# frontscript.net
KiCad netlist of a schematic drawn in Altium Designer
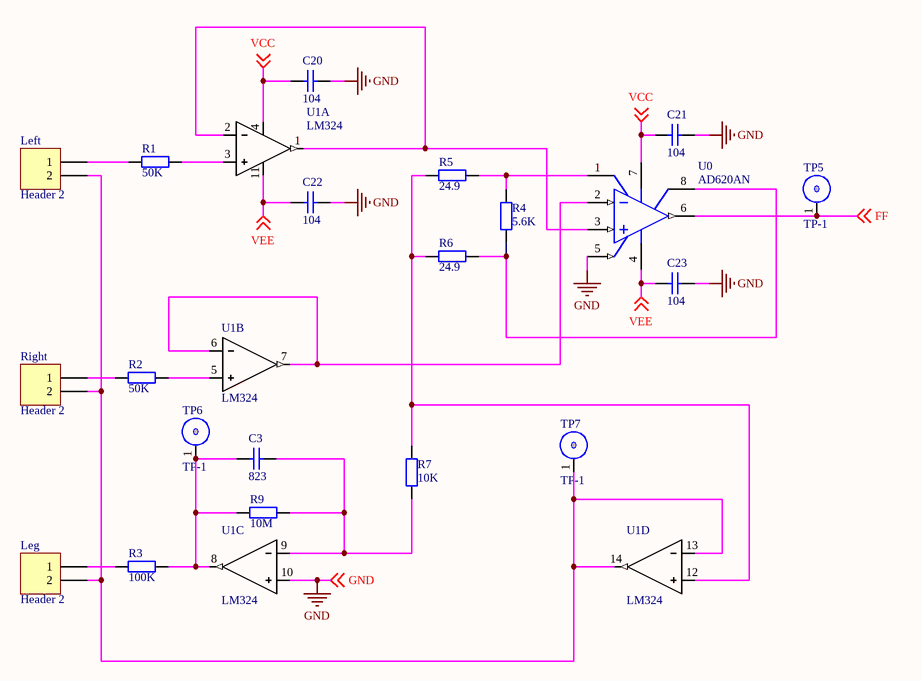
[diagram p0: frontscript.SchDoc]

(export (version "E")
  (design (tool "Eeschema 10.0.6"))
  (components
    (comp (ref "C3")
      (value "823")
      (footprint "C2")
      (description "Capacitor")
      (fields (field (name "PUBLISHER") "Altium Limited"))
      (libsource (lib "ECG") (part "Cap"))
    )
    (comp (ref "C20")
      (value "104")
      (footprint "C2")
      (description "Capacitor")
      (fields (field (name "PUBLISHER") "Altium Limited"))
      (libsource (lib "ECG") (part "Cap"))
    )
    (comp (ref "C21")
      (value "104")
      (footprint "C2")
      (description "Capacitor")
      (fields (field (name "PUBLISHER") "Altium Limited"))
      (libsource (lib "ECG") (part "Cap"))
    )
    (comp (ref "C22")
      (value "104")
      (footprint "C2")
      (description "Capacitor")
      (fields (field (name "PUBLISHER") "Altium Limited"))
      (libsource (lib "ECG") (part "Cap"))
    )
    (comp (ref "C23")
      (value "104")
      (footprint "C2")
      (description "Capacitor")
      (fields (field (name "PUBLISHER") "Altium Limited"))
      (libsource (lib "ECG") (part "Cap"))
    )
    (comp (ref "Left")
      (value "Header 2")
      (footprint "SIP2L")
      (description "Header, 2-Pin")
      (fields (field (name "PUBLISHER") "Altium Limited"))
      (libsource (lib "ECG") (part "Header 2"))
    )
    (comp (ref "Leg")
      (value "Header 2")
      (footprint "SIP2L")
      (description "Header, 2-Pin")
      (fields (field (name "PUBLISHER") "Altium Limited"))
      (libsource (lib "ECG") (part "Header 2"))
    )
    (comp (ref "R1")
      (value "50K")
      (footprint "AXIAL-0.3")
      (description "Resistor")
      (fields (field (name "PUBLISHER") "Altium Limited"))
      (libsource (lib "ECG") (part "Res2"))
    )
    (comp (ref "R2")
      (value "50K")
      (footprint "AXIAL-0.3")
      (description "Resistor")
      (fields (field (name "PUBLISHER") "Altium Limited"))
      (libsource (lib "ECG") (part "Res2"))
    )
    (comp (ref "R3")
      (value "100K")
      (footprint "AXIAL-0.3")
      (description "Resistor")
      (fields (field (name "PUBLISHER") "Altium Limited"))
      (libsource (lib "ECG") (part "Res2"))
    )
    (comp (ref "R4")
      (value "5.6K")
      (footprint "AXIAL-0.3")
      (description "Resistor")
      (fields (field (name "PUBLISHER") "Altium Limited"))
      (libsource (lib "") (part "Res2_1"))
    )
    (comp (ref "R5")
      (value "24.9")
      (footprint "AXIAL-0.3")
      (description "Resistor")
      (fields (field (name "PUBLISHER") "Altium Limited"))
      (libsource (lib "ECG") (part "Res2"))
    )
    (comp (ref "R6")
      (value "24.9")
      (footprint "AXIAL-0.3")
      (description "Resistor")
      (fields (field (name "PUBLISHER") "Altium Limited"))
      (libsource (lib "ECG") (part "Res2"))
    )
    (comp (ref "R7")
      (value "10K")
      (footprint "AXIAL-0.3")
      (description "Resistor")
      (fields (field (name "PUBLISHER") "Altium Limited"))
      (libsource (lib "") (part "Res2_1"))
    )
    (comp (ref "R9")
      (value "10M")
      (footprint "AXIAL-0.3")
      (description "Resistor")
      (fields (field (name "PUBLISHER") "Altium Limited"))
      (libsource (lib "ECG") (part "Res2"))
    )
    (comp (ref "Right")
      (value "Header 2")
      (footprint "SIP2L")
      (description "Header, 2-Pin")
      (fields (field (name "PUBLISHER") "Altium Limited"))
      (libsource (lib "ECG") (part "Header 2"))
    )
    (comp (ref "TP5") (value "TP-1") (footprint "tp-1-1") (libsource (lib "ECG") (part "TP-1")))
    (comp (ref "TP6") (value "TP-1") (footprint "tp-1-1") (libsource (lib "ECG") (part "TP-1")))
    (comp (ref "TP7") (value "TP-1") (footprint "tp-1-1") (libsource (lib "ECG") (part "TP-1")))
    (comp (ref "U0")
      (value "AD620AN")
      (footprint "DIP8")
      (description "Low-Cost, Low-Power Instrumentation Amplifier")
      (fields (field (name "PUBLISHER") "Altium Limited"))
      (libsource (lib "ECG") (part "AD620AN"))
    )
    (comp (ref "U1") (value "LM324") (footprint "ECG:DIP14") (libsource (lib "ECG") (part "LM324")))
  )
  (nets
    (net (code "1") (name "FF") (class "Default")
      (node (ref "TP5") (pin "1") (pintype "passive"))
      (node (ref "U0") (pin "6") (pinfunction "OUT_6") (pintype "output"))
    )
    (net (code "2") (name "GND") (class "Default")
      (node (ref "C20") (pin "2") (pinfunction "2_2") (pintype "passive"))
      (node (ref "C21") (pin "2") (pinfunction "2_2") (pintype "passive"))
      (node (ref "C22") (pin "2") (pinfunction "2_2") (pintype "passive"))
      (node (ref "C23") (pin "2") (pinfunction "2_2") (pintype "passive"))
      (node (ref "U0") (pin "5") (pinfunction "REF_5") (pintype "input"))
      (node (ref "U1") (pin "10") (pinfunction "10_10") (pintype "passive"))
    )
    (net (code "3") (name "Net-(C3-Pad1)") (class "Default")
      (node (ref "C3") (pin "1") (pinfunction "1_1") (pintype "passive"))
      (node (ref "R3") (pin "2") (pinfunction "2_2") (pintype "passive"))
      (node (ref "R9") (pin "1") (pinfunction "1_1") (pintype "passive"))
      (node (ref "TP6") (pin "1") (pintype "passive"))
      (node (ref "U1") (pin "8") (pinfunction "8_8") (pintype "output"))
    )
    (net (code "4") (name "Net-(C3-Pad2)") (class "Default")
      (node (ref "C3") (pin "2") (pinfunction "2_2") (pintype "passive"))
      (node (ref "R7") (pin "1") (pinfunction "1_1") (pintype "passive"))
      (node (ref "R9") (pin "2") (pinfunction "2_2") (pintype "passive"))
      (node (ref "U1") (pin "9") (pinfunction "9_9") (pintype "passive"))
    )
    (net (code "5") (name "Net-(Left-Pad1)") (class "Default")
      (node (ref "Left") (pin "1") (pinfunction "1_1") (pintype "passive"))
      (node (ref "R1") (pin "1") (pinfunction "1_1") (pintype "passive"))
    )
    (net (code "6") (name "Net-(Left-Pad2)") (class "Default")
      (node (ref "Left") (pin "2") (pinfunction "2_2") (pintype "passive"))
      (node (ref "Leg") (pin "2") (pinfunction "2_2") (pintype "passive"))
      (node (ref "Right") (pin "2") (pinfunction "2_2") (pintype "passive"))
      (node (ref "TP7") (pin "1") (pintype "passive"))
      (node (ref "U1") (pin "13") (pinfunction "13_13") (pintype "passive"))
      (node (ref "U1") (pin "14") (pinfunction "14_14") (pintype "output"))
    )
    (net (code "7") (name "Net-(Leg-Pad1)") (class "Default")
      (node (ref "Leg") (pin "1") (pinfunction "1_1") (pintype "passive"))
      (node (ref "R3") (pin "1") (pinfunction "1_1") (pintype "passive"))
    )
    (net (code "8") (name "Net-(R1-Pad2)") (class "Default")
      (node (ref "R1") (pin "2") (pinfunction "2_2") (pintype "passive"))
      (node (ref "U1") (pin "3") (pinfunction "3_3") (pintype "passive"))
    )
    (net (code "9") (name "Net-(R2-Pad1)") (class "Default")
      (node (ref "R2") (pin "1") (pinfunction "1_1") (pintype "passive"))
      (node (ref "Right") (pin "1") (pinfunction "1_1") (pintype "passive"))
    )
    (net (code "10") (name "Net-(R2-Pad2)") (class "Default")
      (node (ref "R2") (pin "2") (pinfunction "2_2") (pintype "passive"))
      (node (ref "U1") (pin "5") (pinfunction "5_5") (pintype "passive"))
    )
    (net (code "11") (name "Net-(R4-Pad1)") (class "Default")
      (node (ref "R4") (pin "1") (pinfunction "1_1") (pintype "passive"))
      (node (ref "R6") (pin "2") (pinfunction "2_2") (pintype "passive"))
      (node (ref "U0") (pin "8") (pinfunction "RG_8") (pintype "passive"))
    )
    (net (code "12") (name "Net-(R4-Pad2)") (class "Default")
      (node (ref "R4") (pin "2") (pinfunction "2_2") (pintype "passive"))
      (node (ref "R5") (pin "2") (pinfunction "2_2") (pintype "passive"))
      (node (ref "U0") (pin "1") (pinfunction "RG_1") (pintype "passive"))
    )
    (net (code "13") (name "Net-(R5-Pad1)") (class "Default")
      (node (ref "R5") (pin "1") (pinfunction "1_1") (pintype "passive"))
      (node (ref "R6") (pin "1") (pinfunction "1_1") (pintype "passive"))
      (node (ref "R7") (pin "2") (pinfunction "2_2") (pintype "passive"))
      (node (ref "U1") (pin "12") (pinfunction "12_12") (pintype "passive"))
    )
    (net (code "14") (name "Net-(U0-+IN)") (class "Default")
      (node (ref "U0") (pin "3") (pinfunction "+IN_3") (pintype "input"))
      (node (ref "U1") (pin "1") (pinfunction "1_1") (pintype "output"))
      (node (ref "U1") (pin "2") (pinfunction "2_2") (pintype "passive"))
    )
    (net (code "15") (name "Net-(U0--IN)") (class "Default")
      (node (ref "U0") (pin "2") (pinfunction "-IN_2") (pintype "input"))
      (node (ref "U1") (pin "6") (pinfunction "6_6") (pintype "passive"))
      (node (ref "U1") (pin "7") (pinfunction "7_7") (pintype "output"))
    )
    (net (code "16") (name "VCC") (class "Default")
      (node (ref "C20") (pin "1") (pinfunction "1_1") (pintype "passive"))
      (node (ref "C21") (pin "1") (pinfunction "1_1") (pintype "passive"))
      (node (ref "U0") (pin "7") (pinfunction "V+_7") (pintype "power_in"))
      (node (ref "U1") (pin "4") (pinfunction "4_4") (pintype "passive"))
    )
    (net (code "17") (name "VEE") (class "Default")
      (node (ref "C22") (pin "1") (pinfunction "1_1") (pintype "passive"))
      (node (ref "C23") (pin "1") (pinfunction "1_1") (pintype "passive"))
      (node (ref "U0") (pin "4") (pinfunction "V-_4") (pintype "power_in"))
      (node (ref "U1") (pin "11") (pinfunction "11_11") (pintype "passive"))
    )
  )
)
